# Mixers.net
KiCad netlist of a schematic drawn in Altium Designer
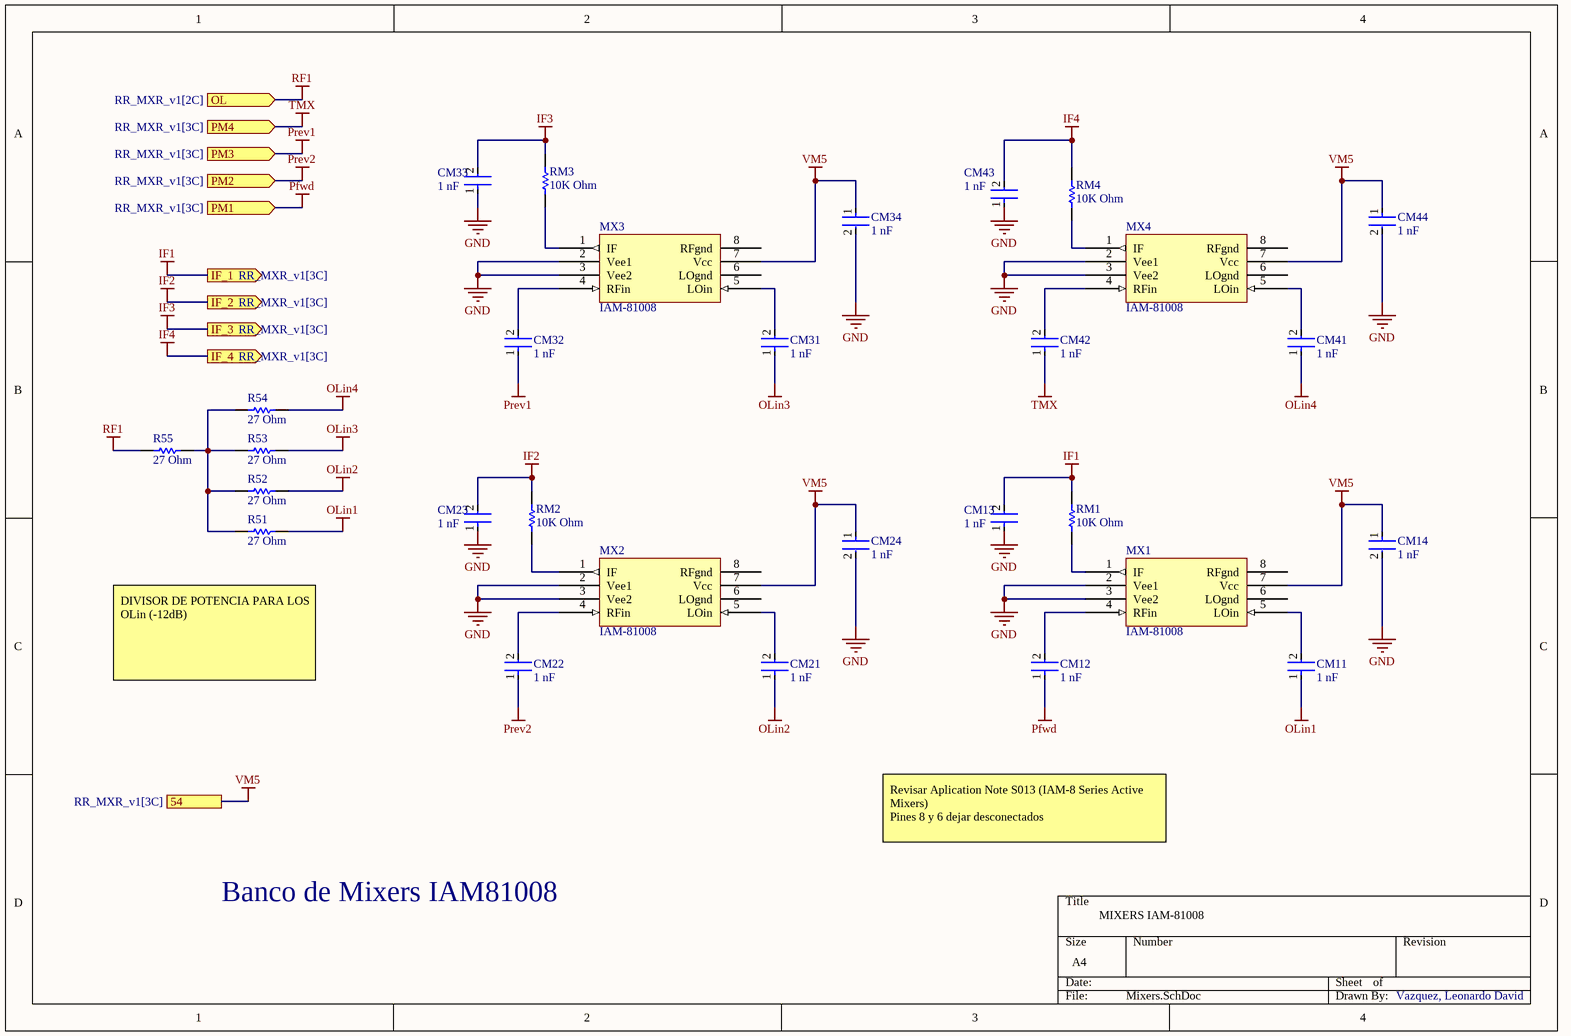
[diagram p0: Mixers.SchDoc]

(export (version "E")
  (design (tool "Eeschema 10.0.6"))
  (components
    (comp (ref "CM11")
      (value "1 nF")
      (footprint "FP-CC0805-0_85-MFG")
      (description "CAP CER 0.1UF 50V X7R 0805")
      (fields (field (name "TOLERANCE") "0.1") (field (name "MANUFACTURER PART NUMBER") "CC0805KRX7R9BB104"))
      (libsource (lib "Altium Content Vault") (part "11868f565c42a9108669ba33697ecf6"))
    )
    (comp (ref "CM12")
      (value "1 nF")
      (footprint "FP-CC0805-0_85-MFG")
      (description "CAP CER 0.1UF 50V X7R 0805")
      (fields (field (name "TOLERANCE") "0.1") (field (name "MANUFACTURER PART NUMBER") "CC0805KRX7R9BB104"))
      (libsource (lib "Altium Content Vault") (part "11868f565c42a9108669ba33697ecf6"))
    )
    (comp (ref "CM13")
      (value "1 nF")
      (footprint "FP-CC0805-0_85-MFG")
      (description "CAP CER 0.1UF 50V X7R 0805")
      (fields (field (name "TOLERANCE") "0.1") (field (name "MANUFACTURER PART NUMBER") "CC0805KRX7R9BB104"))
      (libsource (lib "Altium Content Vault") (part "11868f565c42a9108669ba33697ecf6"))
    )
    (comp (ref "CM14")
      (value "1 nF")
      (footprint "FP-CC0805-0_85-MFG")
      (description "CAP CER 0.1UF 50V X7R 0805")
      (fields (field (name "TOLERANCE") "0.1") (field (name "MANUFACTURER PART NUMBER") "CC0805KRX7R9BB104"))
      (libsource (lib "Altium Content Vault") (part "11868f565c42a9108669ba33697ecf6"))
    )
    (comp (ref "CM21")
      (value "1 nF")
      (footprint "FP-CC0805-0_85-MFG")
      (description "CAP CER 0.1UF 50V X7R 0805")
      (fields (field (name "TOLERANCE") "0.1") (field (name "MANUFACTURER PART NUMBER") "CC0805KRX7R9BB104"))
      (libsource (lib "Altium Content Vault") (part "11868f565c42a9108669ba33697ecf6"))
    )
    (comp (ref "CM22")
      (value "1 nF")
      (footprint "FP-CC0805-0_85-MFG")
      (description "CAP CER 0.1UF 50V X7R 0805")
      (fields (field (name "TOLERANCE") "0.1") (field (name "MANUFACTURER PART NUMBER") "CC0805KRX7R9BB104"))
      (libsource (lib "Altium Content Vault") (part "11868f565c42a9108669ba33697ecf6"))
    )
    (comp (ref "CM23")
      (value "1 nF")
      (footprint "FP-CC0805-0_85-MFG")
      (description "CAP CER 0.1UF 50V X7R 0805")
      (fields (field (name "TOLERANCE") "0.1") (field (name "MANUFACTURER PART NUMBER") "CC0805KRX7R9BB104"))
      (libsource (lib "Altium Content Vault") (part "11868f565c42a9108669ba33697ecf6"))
    )
    (comp (ref "CM24")
      (value "1 nF")
      (footprint "FP-CC0805-0_85-MFG")
      (description "CAP CER 0.1UF 50V X7R 0805")
      (fields (field (name "TOLERANCE") "0.1") (field (name "MANUFACTURER PART NUMBER") "CC0805KRX7R9BB104"))
      (libsource (lib "Altium Content Vault") (part "11868f565c42a9108669ba33697ecf6"))
    )
    (comp (ref "CM31")
      (value "1 nF")
      (footprint "FP-CC0805-0_85-MFG")
      (description "CAP CER 0.1UF 50V X7R 0805")
      (fields (field (name "TOLERANCE") "0.1") (field (name "MANUFACTURER PART NUMBER") "CC0805KRX7R9BB104"))
      (libsource (lib "Altium Content Vault") (part "11868f565c42a9108669ba33697ecf6"))
    )
    (comp (ref "CM32")
      (value "1 nF")
      (footprint "FP-CC0805-0_85-MFG")
      (description "CAP CER 0.1UF 50V X7R 0805")
      (fields (field (name "TOLERANCE") "0.1") (field (name "MANUFACTURER PART NUMBER") "CC0805KRX7R9BB104"))
      (libsource (lib "Altium Content Vault") (part "11868f565c42a9108669ba33697ecf6"))
    )
    (comp (ref "CM33")
      (value "1 nF")
      (footprint "FP-CC0805-0_85-MFG")
      (description "CAP CER 0.1UF 50V X7R 0805")
      (fields (field (name "TOLERANCE") "0.1") (field (name "MANUFACTURER PART NUMBER") "CC0805KRX7R9BB104"))
      (libsource (lib "Altium Content Vault") (part "11868f565c42a9108669ba33697ecf6"))
    )
    (comp (ref "CM34")
      (value "1 nF")
      (footprint "FP-CC0805-0_85-MFG")
      (description "CAP CER 0.1UF 50V X7R 0805")
      (fields (field (name "TOLERANCE") "0.1") (field (name "MANUFACTURER PART NUMBER") "CC0805KRX7R9BB104"))
      (libsource (lib "Altium Content Vault") (part "11868f565c42a9108669ba33697ecf6"))
    )
    (comp (ref "CM41")
      (value "1 nF")
      (footprint "FP-CC0805-0_85-MFG")
      (description "CAP CER 0.1UF 50V X7R 0805")
      (fields (field (name "TOLERANCE") "0.1") (field (name "MANUFACTURER PART NUMBER") "CC0805KRX7R9BB104"))
      (libsource (lib "Altium Content Vault") (part "11868f565c42a9108669ba33697ecf6"))
    )
    (comp (ref "CM42")
      (value "1 nF")
      (footprint "FP-CC0805-0_85-MFG")
      (description "CAP CER 0.1UF 50V X7R 0805")
      (fields (field (name "TOLERANCE") "0.1") (field (name "MANUFACTURER PART NUMBER") "CC0805KRX7R9BB104"))
      (libsource (lib "Altium Content Vault") (part "11868f565c42a9108669ba33697ecf6"))
    )
    (comp (ref "CM43")
      (value "1 nF")
      (footprint "FP-CC0805-0_85-MFG")
      (description "CAP CER 0.1UF 50V X7R 0805")
      (fields (field (name "TOLERANCE") "0.1") (field (name "MANUFACTURER PART NUMBER") "CC0805KRX7R9BB104"))
      (libsource (lib "Altium Content Vault") (part "11868f565c42a9108669ba33697ecf6"))
    )
    (comp (ref "CM44")
      (value "1 nF")
      (footprint "FP-CC0805-0_85-MFG")
      (description "CAP CER 0.1UF 50V X7R 0805")
      (fields (field (name "TOLERANCE") "0.1") (field (name "MANUFACTURER PART NUMBER") "CC0805KRX7R9BB104"))
      (libsource (lib "Altium Content Vault") (part "11868f565c42a9108669ba33697ecf6"))
    )
    (comp (ref "MX1")
      (value "IAM-81008")
      (footprint "PcbLib1:IAM-81008")
      (description "mixer")
      (libsource (lib "Schlib1") (part "IAM-81008"))
    )
    (comp (ref "MX2")
      (value "IAM-81008")
      (footprint "PcbLib1:IAM-81008")
      (description "mixer")
      (libsource (lib "Schlib1") (part "IAM-81008"))
    )
    (comp (ref "MX3")
      (value "IAM-81008")
      (footprint "PcbLib1:IAM-81008")
      (description "mixer")
      (libsource (lib "Schlib1") (part "IAM-81008"))
    )
    (comp (ref "MX4")
      (value "IAM-81008")
      (footprint "PcbLib1:IAM-81008")
      (description "mixer")
      (libsource (lib "Schlib1") (part "IAM-81008"))
    )
    (comp (ref "R51")
      (value "27 Ohm")
      (footprint "RESC2013X60X40ML20T25")
      (fields (field (name "MANUFACTURER") "Panasonic") (field (name "PART NUMBER") "ERA6AEB101V"))
      (libsource (lib "Altium Content Vault") (part "RES"))
    )
    (comp (ref "R52")
      (value "27 Ohm")
      (footprint "RESC2013X60X40ML20T25")
      (fields (field (name "MANUFACTURER") "Panasonic") (field (name "PART NUMBER") "ERA6AEB101V"))
      (libsource (lib "Altium Content Vault") (part "RES"))
    )
    (comp (ref "R53")
      (value "27 Ohm")
      (footprint "RESC2013X60X40ML20T25")
      (fields (field (name "MANUFACTURER") "Panasonic") (field (name "PART NUMBER") "ERA6AEB101V"))
      (libsource (lib "Altium Content Vault") (part "RES"))
    )
    (comp (ref "R54")
      (value "27 Ohm")
      (footprint "RESC2013X60X40ML20T25")
      (fields (field (name "MANUFACTURER") "Panasonic") (field (name "PART NUMBER") "ERA6AEB101V"))
      (libsource (lib "Altium Content Vault") (part "RES"))
    )
    (comp (ref "R55")
      (value "27 Ohm")
      (footprint "RESC2013X60X40ML20T25")
      (fields (field (name "MANUFACTURER") "Panasonic") (field (name "PART NUMBER") "ERA6AEB101V"))
      (libsource (lib "Altium Content Vault") (part "RES"))
    )
    (comp (ref "RM1")
      (value "10K Ohm")
      (footprint "RESC2013X60X40ML20T25")
      (fields (field (name "MANUFACTURER") "Panasonic") (field (name "PART NUMBER") "ERA6AEB101V"))
      (libsource (lib "Altium Content Vault") (part "RES"))
    )
    (comp (ref "RM2")
      (value "10K Ohm")
      (footprint "RESC2013X60X40ML20T25")
      (fields (field (name "MANUFACTURER") "Panasonic") (field (name "PART NUMBER") "ERA6AEB101V"))
      (libsource (lib "Altium Content Vault") (part "RES"))
    )
    (comp (ref "RM3")
      (value "10K Ohm")
      (footprint "RESC2013X60X40ML20T25")
      (fields (field (name "MANUFACTURER") "Panasonic") (field (name "PART NUMBER") "ERA6AEB101V"))
      (libsource (lib "Altium Content Vault") (part "RES"))
    )
    (comp (ref "RM4")
      (value "10K Ohm")
      (footprint "RESC2013X60X40ML20T25")
      (fields (field (name "MANUFACTURER") "Panasonic") (field (name "PART NUMBER") "ERA6AEB101V"))
      (libsource (lib "Altium Content Vault") (part "RES"))
    )
  )
  (nets
    (net (code "1") (name "GND") (class "Default")
      (node (ref "CM13") (pin "1") (pinfunction "1_1") (pintype "passive"))
      (node (ref "CM14") (pin "2") (pinfunction "2_2") (pintype "passive"))
      (node (ref "CM23") (pin "1") (pinfunction "1_1") (pintype "passive"))
      (node (ref "CM24") (pin "2") (pinfunction "2_2") (pintype "passive"))
      (node (ref "CM33") (pin "1") (pinfunction "1_1") (pintype "passive"))
      (node (ref "CM34") (pin "2") (pinfunction "2_2") (pintype "passive"))
      (node (ref "CM43") (pin "1") (pinfunction "1_1") (pintype "passive"))
      (node (ref "CM44") (pin "2") (pinfunction "2_2") (pintype "passive"))
      (node (ref "MX1") (pin "2") (pinfunction "Vee1_2") (pintype "power_in"))
      (node (ref "MX1") (pin "3") (pinfunction "Vee2_3") (pintype "power_in"))
      (node (ref "MX2") (pin "2") (pinfunction "Vee1_2") (pintype "power_in"))
      (node (ref "MX2") (pin "3") (pinfunction "Vee2_3") (pintype "power_in"))
      (node (ref "MX3") (pin "2") (pinfunction "Vee1_2") (pintype "power_in"))
      (node (ref "MX3") (pin "3") (pinfunction "Vee2_3") (pintype "power_in"))
      (node (ref "MX4") (pin "2") (pinfunction "Vee1_2") (pintype "power_in"))
      (node (ref "MX4") (pin "3") (pinfunction "Vee2_3") (pintype "power_in"))
    )
    (net (code "2") (name "IF1") (class "Default")
      (node (ref "CM13") (pin "2") (pinfunction "2_2") (pintype "passive"))
      (node (ref "RM1") (pin "1") (pinfunction "1_1") (pintype "passive"))
    )
    (net (code "3") (name "IF2") (class "Default")
      (node (ref "CM23") (pin "2") (pinfunction "2_2") (pintype "passive"))
      (node (ref "RM2") (pin "1") (pinfunction "1_1") (pintype "passive"))
    )
    (net (code "4") (name "IF3") (class "Default")
      (node (ref "CM33") (pin "2") (pinfunction "2_2") (pintype "passive"))
      (node (ref "RM3") (pin "1") (pinfunction "1_1") (pintype "passive"))
    )
    (net (code "5") (name "IF4") (class "Default")
      (node (ref "CM43") (pin "2") (pinfunction "2_2") (pintype "passive"))
      (node (ref "RM4") (pin "1") (pinfunction "1_1") (pintype "passive"))
    )
    (net (code "6") (name "Net-(MX1-IF)") (class "Default")
      (node (ref "MX1") (pin "1") (pinfunction "IF_1") (pintype "output"))
      (node (ref "RM1") (pin "2") (pinfunction "2_2") (pintype "passive"))
    )
    (net (code "7") (name "Net-(MX1-LOin)") (class "Default")
      (node (ref "CM11") (pin "2") (pinfunction "2_2") (pintype "passive"))
      (node (ref "MX1") (pin "5") (pinfunction "LOin_5") (pintype "input"))
    )
    (net (code "8") (name "Net-(MX1-RFin)") (class "Default")
      (node (ref "CM12") (pin "2") (pinfunction "2_2") (pintype "passive"))
      (node (ref "MX1") (pin "4") (pinfunction "RFin_4") (pintype "input"))
    )
    (net (code "9") (name "Net-(MX2-IF)") (class "Default")
      (node (ref "MX2") (pin "1") (pinfunction "IF_1") (pintype "output"))
      (node (ref "RM2") (pin "2") (pinfunction "2_2") (pintype "passive"))
    )
    (net (code "10") (name "Net-(MX2-LOin)") (class "Default")
      (node (ref "CM21") (pin "2") (pinfunction "2_2") (pintype "passive"))
      (node (ref "MX2") (pin "5") (pinfunction "LOin_5") (pintype "input"))
    )
    (net (code "11") (name "Net-(MX2-RFin)") (class "Default")
      (node (ref "CM22") (pin "2") (pinfunction "2_2") (pintype "passive"))
      (node (ref "MX2") (pin "4") (pinfunction "RFin_4") (pintype "input"))
    )
    (net (code "12") (name "Net-(MX3-IF)") (class "Default")
      (node (ref "MX3") (pin "1") (pinfunction "IF_1") (pintype "output"))
      (node (ref "RM3") (pin "2") (pinfunction "2_2") (pintype "passive"))
    )
    (net (code "13") (name "Net-(MX3-LOin)") (class "Default")
      (node (ref "CM31") (pin "2") (pinfunction "2_2") (pintype "passive"))
      (node (ref "MX3") (pin "5") (pinfunction "LOin_5") (pintype "input"))
    )
    (net (code "14") (name "Net-(MX3-RFin)") (class "Default")
      (node (ref "CM32") (pin "2") (pinfunction "2_2") (pintype "passive"))
      (node (ref "MX3") (pin "4") (pinfunction "RFin_4") (pintype "input"))
    )
    (net (code "15") (name "Net-(MX4-IF)") (class "Default")
      (node (ref "MX4") (pin "1") (pinfunction "IF_1") (pintype "output"))
      (node (ref "RM4") (pin "2") (pinfunction "2_2") (pintype "passive"))
    )
    (net (code "16") (name "Net-(MX4-LOin)") (class "Default")
      (node (ref "CM41") (pin "2") (pinfunction "2_2") (pintype "passive"))
      (node (ref "MX4") (pin "5") (pinfunction "LOin_5") (pintype "input"))
    )
    (net (code "17") (name "Net-(MX4-RFin)") (class "Default")
      (node (ref "CM42") (pin "2") (pinfunction "2_2") (pintype "passive"))
      (node (ref "MX4") (pin "4") (pinfunction "RFin_4") (pintype "input"))
    )
    (net (code "18") (name "Net-(R51-Pad2)") (class "Default")
      (node (ref "R51") (pin "2") (pinfunction "2_2") (pintype "passive"))
      (node (ref "R52") (pin "2") (pinfunction "2_2") (pintype "passive"))
      (node (ref "R53") (pin "2") (pinfunction "2_2") (pintype "passive"))
      (node (ref "R54") (pin "2") (pinfunction "2_2") (pintype "passive"))
      (node (ref "R55") (pin "1") (pinfunction "1_1") (pintype "passive"))
    )
    (net (code "19") (name "OLin1") (class "Default")
      (node (ref "CM11") (pin "1") (pinfunction "1_1") (pintype "passive"))
      (node (ref "R51") (pin "1") (pinfunction "1_1") (pintype "passive"))
    )
    (net (code "20") (name "OLin2") (class "Default")
      (node (ref "CM21") (pin "1") (pinfunction "1_1") (pintype "passive"))
      (node (ref "R52") (pin "1") (pinfunction "1_1") (pintype "passive"))
    )
    (net (code "21") (name "OLin3") (class "Default")
      (node (ref "CM31") (pin "1") (pinfunction "1_1") (pintype "passive"))
      (node (ref "R53") (pin "1") (pinfunction "1_1") (pintype "passive"))
    )
    (net (code "22") (name "OLin4") (class "Default")
      (node (ref "CM41") (pin "1") (pinfunction "1_1") (pintype "passive"))
      (node (ref "R54") (pin "1") (pinfunction "1_1") (pintype "passive"))
    )
    (net (code "23") (name "Pfwd") (class "Default")
      (node (ref "CM12") (pin "1") (pinfunction "1_1") (pintype "passive"))
    )
    (net (code "24") (name "Prev1") (class "Default")
      (node (ref "CM32") (pin "1") (pinfunction "1_1") (pintype "passive"))
    )
    (net (code "25") (name "Prev2") (class "Default")
      (node (ref "CM22") (pin "1") (pinfunction "1_1") (pintype "passive"))
    )
    (net (code "26") (name "RF1") (class "Default")
      (node (ref "R55") (pin "2") (pinfunction "2_2") (pintype "passive"))
    )
    (net (code "27") (name "TMX") (class "Default")
      (node (ref "CM42") (pin "1") (pinfunction "1_1") (pintype "passive"))
    )
    (net (code "28") (name "VM5") (class "Default")
      (node (ref "CM14") (pin "1") (pinfunction "1_1") (pintype "passive"))
      (node (ref "CM24") (pin "1") (pinfunction "1_1") (pintype "passive"))
      (node (ref "CM34") (pin "1") (pinfunction "1_1") (pintype "passive"))
      (node (ref "CM44") (pin "1") (pinfunction "1_1") (pintype "passive"))
      (node (ref "MX1") (pin "7") (pinfunction "Vcc_7") (pintype "power_in"))
      (node (ref "MX2") (pin "7") (pinfunction "Vcc_7") (pintype "power_in"))
      (node (ref "MX3") (pin "7") (pinfunction "Vcc_7") (pintype "power_in"))
      (node (ref "MX4") (pin "7") (pinfunction "Vcc_7") (pintype "power_in"))
    )
    (net (code "29") (name "unconnected-(MX1-LOgnd-Pad6)") (class "Default")
      (node (ref "MX1") (pin "6") (pinfunction "LOgnd_6") (pintype "power_in"))
    )
    (net (code "30") (name "unconnected-(MX1-RFgnd-Pad8)") (class "Default")
      (node (ref "MX1") (pin "8") (pinfunction "RFgnd_8") (pintype "power_in"))
    )
    (net (code "31") (name "unconnected-(MX2-LOgnd-Pad6)") (class "Default")
      (node (ref "MX2") (pin "6") (pinfunction "LOgnd_6") (pintype "power_in"))
    )
    (net (code "32") (name "unconnected-(MX2-RFgnd-Pad8)") (class "Default")
      (node (ref "MX2") (pin "8") (pinfunction "RFgnd_8") (pintype "power_in"))
    )
    (net (code "33") (name "unconnected-(MX3-LOgnd-Pad6)") (class "Default")
      (node (ref "MX3") (pin "6") (pinfunction "LOgnd_6") (pintype "power_in"))
    )
    (net (code "34") (name "unconnected-(MX3-RFgnd-Pad8)") (class "Default")
      (node (ref "MX3") (pin "8") (pinfunction "RFgnd_8") (pintype "power_in"))
    )
    (net (code "35") (name "unconnected-(MX4-LOgnd-Pad6)") (class "Default")
      (node (ref "MX4") (pin "6") (pinfunction "LOgnd_6") (pintype "power_in"))
    )
    (net (code "36") (name "unconnected-(MX4-RFgnd-Pad8)") (class "Default")
      (node (ref "MX4") (pin "8") (pinfunction "RFgnd_8") (pintype "power_in"))
    )
  )
)
